# Tr_Final.net
KiCad netlist of a schematic drawn in EAGLE
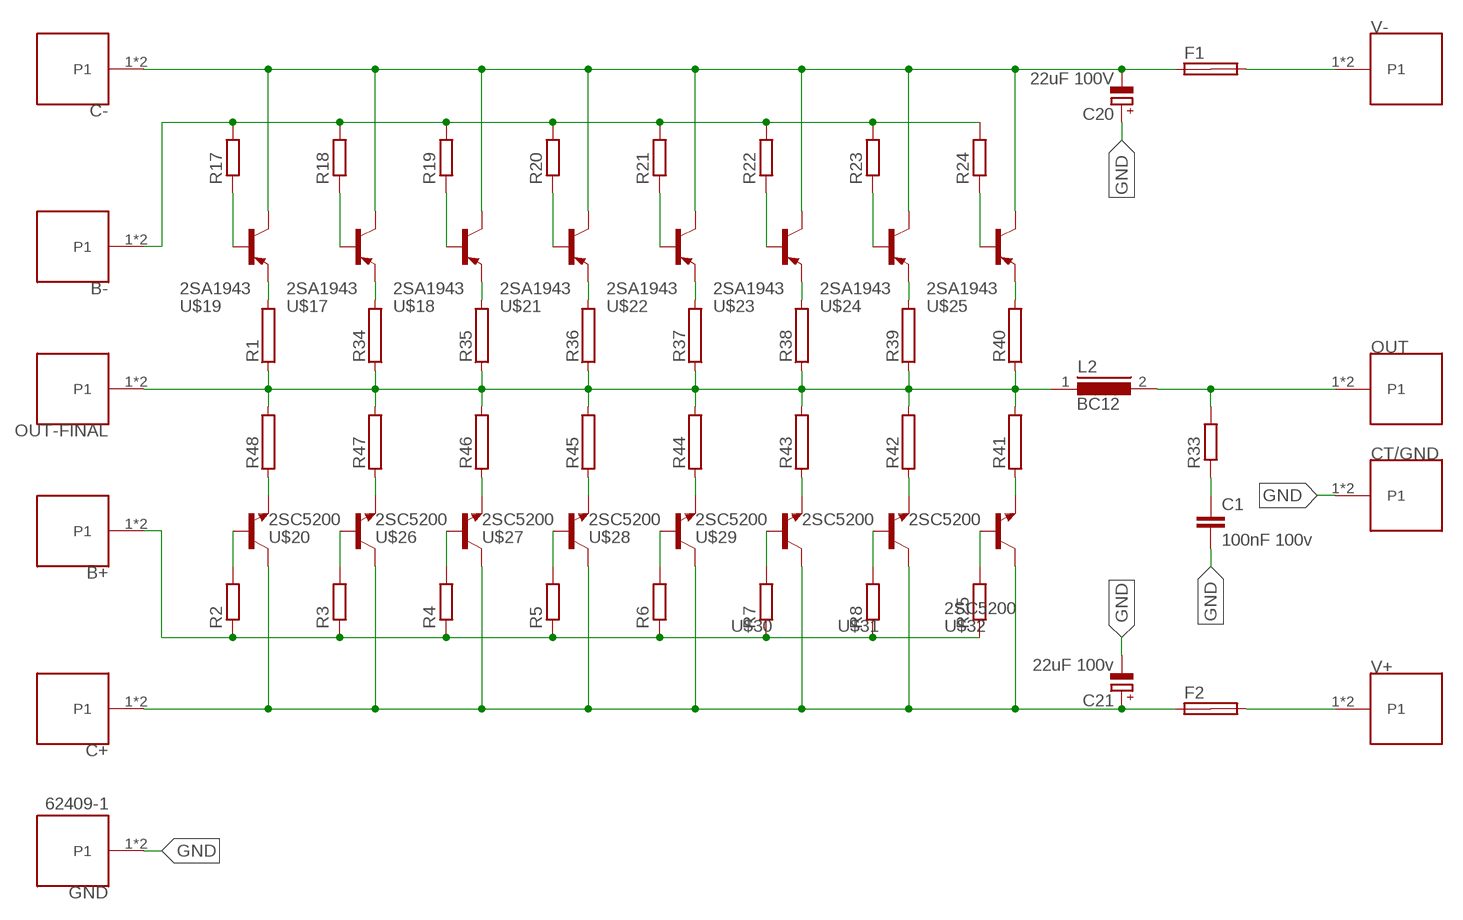
[diagram p0: schematic, sheet 1]

(export (version "E")
  (design (tool "Eeschema 10.0.6"))
  (components
    (comp (ref "B+")
      (value "62409-1")
      (footprint "eagle-import:TE_62409-1")
      (fields (field (name "MF") "TE Connectivity"))
      (libsource (lib "eagle-import") (part "62409-1"))
    )
    (comp (ref "B-")
      (value "62409-1")
      (footprint "eagle-import:TE_62409-1")
      (fields (field (name "MF") "TE Connectivity"))
      (libsource (lib "eagle-import") (part "62409-1"))
    )
    (comp (ref "C+")
      (value "62409-1")
      (footprint "eagle-import:TE_62409-1")
      (fields (field (name "MF") "TE Connectivity"))
      (libsource (lib "eagle-import") (part "62409-1"))
    )
    (comp (ref "C-")
      (value "SKUN")
      (footprint "eagle-import:TE_62409-1")
      (fields (field (name "COMMENT") "62409-1") (field (name "MF") "TE Connectivity"))
      (libsource (lib "eagle-import") (part "62409-1"))
    )
    (comp (ref "C1")
      (value "100nF 100v")
      (footprint "eagle-import:C7.5B5")
      (libsource (lib "eagle-import") (part "C7.5/5"))
    )
    (comp (ref "C20")
      (value "22uF 100V")
      (footprint "eagle-import:E3,5-8")
      (libsource (lib "eagle-import") (part "CPOL-EUE3.5-8"))
    )
    (comp (ref "C21")
      (value "22uF 100v")
      (footprint "eagle-import:E3,5-8")
      (libsource (lib "eagle-import") (part "CPOL-EUE3.5-8"))
    )
    (comp (ref "CT/GND")
      (value "62409-1")
      (footprint "eagle-import:TE_62409-1")
      (fields (field (name "MF") "TE Connectivity"))
      (libsource (lib "eagle-import") (part "62409-1"))
    )
    (comp (ref "F1")
      (value "SHK20L")
      (footprint "eagle-import:SHK20L")
      (libsource (lib "eagle-import") (part "SHK20L"))
    )
    (comp (ref "F2")
      (value "SHK20L")
      (footprint "eagle-import:SHK20L")
      (libsource (lib "eagle-import") (part "SHK20L"))
    )
    (comp (ref "GND")
      (value "62409-1")
      (footprint "eagle-import:TE_62409-1")
      (fields (field (name "MF") "TE Connectivity"))
      (libsource (lib "eagle-import") (part "62409-1"))
    )
    (comp (ref "L2")
      (value "BC12")
      (footprint "eagle-import:BC12")
      (libsource (lib "eagle-import") (part "BC12"))
    )
    (comp (ref "OUT")
      (value "62409-1")
      (footprint "eagle-import:TE_62409-1")
      (fields (field (name "MF") "TE Connectivity"))
      (libsource (lib "eagle-import") (part "62409-1"))
    )
    (comp (ref "OUT-FINAL")
      (value "62409-1")
      (footprint "eagle-import:TE_62409-1")
      (fields (field (name "MF") "TE Connectivity"))
      (libsource (lib "eagle-import") (part "62409-1"))
    )
    (comp (ref "R1")
      (value "RMG100-V")
      (footprint "eagle-import:TO-247-2V")
      (libsource (lib "eagle-import") (part "RMG100-V"))
    )
    (comp (ref "R2")
      (value "R-EU_0207/15")
      (footprint "eagle-import:0207_15")
      (libsource (lib "eagle-import") (part "resistor coba_R-EU_0207/15"))
    )
    (comp (ref "R3")
      (value "R-EU_0207/15")
      (footprint "eagle-import:0207_15")
      (libsource (lib "eagle-import") (part "resistor coba_R-EU_0207/15"))
    )
    (comp (ref "R4")
      (value "R-EU_0207/15")
      (footprint "eagle-import:0207_15")
      (libsource (lib "eagle-import") (part "resistor coba_R-EU_0207/15"))
    )
    (comp (ref "R5")
      (value "R-EU_0207/15")
      (footprint "eagle-import:0207_15")
      (libsource (lib "eagle-import") (part "resistor coba_R-EU_0207/15"))
    )
    (comp (ref "R6")
      (value "R-EU_0207/15")
      (footprint "eagle-import:0207_15")
      (libsource (lib "eagle-import") (part "resistor coba_R-EU_0207/15"))
    )
    (comp (ref "R7")
      (value "R-EU_0207/15")
      (footprint "eagle-import:0207_15")
      (libsource (lib "eagle-import") (part "resistor coba_R-EU_0207/15"))
    )
    (comp (ref "R8")
      (value "R-EU_0207/15")
      (footprint "eagle-import:0207_15")
      (libsource (lib "eagle-import") (part "resistor coba_R-EU_0207/15"))
    )
    (comp (ref "R17")
      (value "R-EU_0207/15")
      (footprint "eagle-import:0207_15")
      (libsource (lib "eagle-import") (part "resistor coba_R-EU_0207/15"))
    )
    (comp (ref "R18")
      (value "R-EU_0207/15")
      (footprint "eagle-import:0207_15")
      (libsource (lib "eagle-import") (part "resistor coba_R-EU_0207/15"))
    )
    (comp (ref "R19")
      (value "R-EU_0207/15")
      (footprint "eagle-import:0207_15")
      (libsource (lib "eagle-import") (part "resistor coba_R-EU_0207/15"))
    )
    (comp (ref "R20")
      (value "R-EU_0207/15")
      (footprint "eagle-import:0207_15")
      (libsource (lib "eagle-import") (part "resistor coba_R-EU_0207/15"))
    )
    (comp (ref "R21")
      (value "R-EU_0207/15")
      (footprint "eagle-import:0207_15")
      (libsource (lib "eagle-import") (part "resistor coba_R-EU_0207/15"))
    )
    (comp (ref "R22")
      (value "R-EU_0207/15")
      (footprint "eagle-import:0207_15")
      (libsource (lib "eagle-import") (part "resistor coba_R-EU_0207/15"))
    )
    (comp (ref "R23")
      (value "R-EU_0207/15")
      (footprint "eagle-import:0207_15")
      (libsource (lib "eagle-import") (part "resistor coba_R-EU_0207/15"))
    )
    (comp (ref "R24")
      (value "R-EU_0207/15")
      (footprint "eagle-import:0207_15")
      (libsource (lib "eagle-import") (part "resistor coba_R-EU_0207/15"))
    )
    (comp (ref "R25")
      (value "R-EU_0207/15")
      (footprint "eagle-import:0207_15")
      (libsource (lib "eagle-import") (part "resistor coba_R-EU_0207/15"))
    )
    (comp (ref "R33")
      (value "R-EU_0617/22")
      (footprint "eagle-import:0617_22")
      (libsource (lib "eagle-import") (part "R-EU_0617/22"))
    )
    (comp (ref "R34")
      (value "RMG100-V")
      (footprint "eagle-import:TO-247-2V")
      (libsource (lib "eagle-import") (part "RMG100-V"))
    )
    (comp (ref "R35")
      (value "RMG100-V")
      (footprint "eagle-import:TO-247-2V")
      (libsource (lib "eagle-import") (part "RMG100-V"))
    )
    (comp (ref "R36")
      (value "RMG100-V")
      (footprint "eagle-import:TO-247-2V")
      (libsource (lib "eagle-import") (part "RMG100-V"))
    )
    (comp (ref "R37")
      (value "RMG100-V")
      (footprint "eagle-import:TO-247-2V")
      (libsource (lib "eagle-import") (part "RMG100-V"))
    )
    (comp (ref "R38")
      (value "RMG100-V")
      (footprint "eagle-import:TO-247-2V")
      (libsource (lib "eagle-import") (part "RMG100-V"))
    )
    (comp (ref "R39")
      (value "RMG100-V")
      (footprint "eagle-import:TO-247-2V")
      (libsource (lib "eagle-import") (part "RMG100-V"))
    )
    (comp (ref "R40")
      (value "RMG100-V")
      (footprint "eagle-import:TO-247-2V")
      (libsource (lib "eagle-import") (part "RMG100-V"))
    )
    (comp (ref "R41")
      (value "RMG100-V")
      (footprint "eagle-import:TO-247-2V")
      (libsource (lib "eagle-import") (part "RMG100-V"))
    )
    (comp (ref "R42")
      (value "RMG100-V")
      (footprint "eagle-import:TO-247-2V")
      (libsource (lib "eagle-import") (part "RMG100-V"))
    )
    (comp (ref "R43")
      (value "RMG100-V")
      (footprint "eagle-import:TO-247-2V")
      (libsource (lib "eagle-import") (part "RMG100-V"))
    )
    (comp (ref "R44")
      (value "RMG100-V")
      (footprint "eagle-import:TO-247-2V")
      (libsource (lib "eagle-import") (part "RMG100-V"))
    )
    (comp (ref "R45")
      (value "RMG100-V")
      (footprint "eagle-import:TO-247-2V")
      (libsource (lib "eagle-import") (part "RMG100-V"))
    )
    (comp (ref "R46")
      (value "RMG100-V")
      (footprint "eagle-import:TO-247-2V")
      (libsource (lib "eagle-import") (part "RMG100-V"))
    )
    (comp (ref "R47")
      (value "RMG100-V")
      (footprint "eagle-import:TO-247-2V")
      (libsource (lib "eagle-import") (part "RMG100-V"))
    )
    (comp (ref "R48")
      (value "RMG100-V")
      (footprint "eagle-import:TO-247-2V")
      (libsource (lib "eagle-import") (part "RMG100-V"))
    )
    (comp (ref "U$17")
      (value "2SA1943")
      (footprint "eagle-import:TO-264")
      (libsource (lib "eagle-import") (part "2SA1943"))
    )
    (comp (ref "U$18")
      (value "2SA1943")
      (footprint "eagle-import:TO-264")
      (libsource (lib "eagle-import") (part "2SA1943"))
    )
    (comp (ref "U$19")
      (value "2SA1943")
      (footprint "eagle-import:TO-264")
      (libsource (lib "eagle-import") (part "2SA1943"))
    )
    (comp (ref "U$20")
      (value "2SC5200")
      (footprint "eagle-import:TO-264")
      (libsource (lib "eagle-import") (part "2SC5200"))
    )
    (comp (ref "U$21")
      (value "2SA1943")
      (footprint "eagle-import:TO-264")
      (libsource (lib "eagle-import") (part "2SA1943"))
    )
    (comp (ref "U$22")
      (value "2SA1943")
      (footprint "eagle-import:TO-264")
      (libsource (lib "eagle-import") (part "2SA1943"))
    )
    (comp (ref "U$23")
      (value "2SA1943")
      (footprint "eagle-import:TO-264")
      (libsource (lib "eagle-import") (part "2SA1943"))
    )
    (comp (ref "U$24")
      (value "2SA1943")
      (footprint "eagle-import:TO-264")
      (libsource (lib "eagle-import") (part "2SA1943"))
    )
    (comp (ref "U$25")
      (value "2SA1943")
      (footprint "eagle-import:TO-264")
      (libsource (lib "eagle-import") (part "2SA1943"))
    )
    (comp (ref "U$26")
      (value "2SC5200")
      (footprint "eagle-import:TO-264")
      (libsource (lib "eagle-import") (part "2SC5200"))
    )
    (comp (ref "U$27")
      (value "2SC5200")
      (footprint "eagle-import:TO-264")
      (libsource (lib "eagle-import") (part "2SC5200"))
    )
    (comp (ref "U$28")
      (value "2SC5200")
      (footprint "eagle-import:TO-264")
      (libsource (lib "eagle-import") (part "2SC5200"))
    )
    (comp (ref "U$29")
      (value "2SC5200")
      (footprint "eagle-import:TO-264")
      (libsource (lib "eagle-import") (part "2SC5200"))
    )
    (comp (ref "U$30")
      (value "2SC5200")
      (footprint "eagle-import:TO-264")
      (libsource (lib "eagle-import") (part "2SC5200"))
    )
    (comp (ref "U$31")
      (value "2SC5200")
      (footprint "eagle-import:TO-264")
      (libsource (lib "eagle-import") (part "2SC5200"))
    )
    (comp (ref "U$32")
      (value "2SC5200")
      (footprint "eagle-import:TO-264")
      (libsource (lib "eagle-import") (part "2SC5200"))
    )
    (comp (ref "V+")
      (value "62409-1")
      (footprint "eagle-import:TE_62409-1")
      (fields (field (name "MF") "TE Connectivity"))
      (libsource (lib "eagle-import") (part "62409-1"))
    )
    (comp (ref "V-")
      (value "62409-1")
      (footprint "eagle-import:TE_62409-1")
      (fields (field (name "MF") "TE Connectivity"))
      (libsource (lib "eagle-import") (part "62409-1"))
    )
  )
  (nets
    (net (code "1") (name "GND") (class "Default")
      (node (ref "C1") (pin "2") (pinfunction "2_2") (pintype "passive"))
      (node (ref "C20") (pin "+") (pinfunction "+_+") (pintype "passive"))
      (node (ref "C21") (pin "-") (pinfunction "-_-") (pintype "passive"))
      (node (ref "CT/GND") (pin "1") (pinfunction "P1_1") (pintype "passive"))
      (node (ref "CT/GND") (pin "2") (pinfunction "P1_2") (pintype "passive"))
      (node (ref "GND") (pin "1") (pinfunction "P1_1") (pintype "passive"))
      (node (ref "GND") (pin "2") (pinfunction "P1_2") (pintype "passive"))
    )
    (net (code "2") (name "Net-(B+-P1-Pad1)") (class "Default")
      (node (ref "B+") (pin "1") (pinfunction "P1_1") (pintype "passive"))
      (node (ref "B+") (pin "2") (pinfunction "P1_2") (pintype "passive"))
      (node (ref "R2") (pin "1") (pinfunction "1_1") (pintype "passive"))
      (node (ref "R25") (pin "1") (pinfunction "1_1") (pintype "passive"))
      (node (ref "R3") (pin "1") (pinfunction "1_1") (pintype "passive"))
      (node (ref "R4") (pin "1") (pinfunction "1_1") (pintype "passive"))
      (node (ref "R5") (pin "1") (pinfunction "1_1") (pintype "passive"))
      (node (ref "R6") (pin "1") (pinfunction "1_1") (pintype "passive"))
      (node (ref "R7") (pin "1") (pinfunction "1_1") (pintype "passive"))
      (node (ref "R8") (pin "1") (pinfunction "1_1") (pintype "passive"))
    )
    (net (code "3") (name "Net-(B--P1-Pad1)") (class "Default")
      (node (ref "B-") (pin "1") (pinfunction "P1_1") (pintype "passive"))
      (node (ref "B-") (pin "2") (pinfunction "P1_2") (pintype "passive"))
      (node (ref "R17") (pin "2") (pinfunction "2_2") (pintype "passive"))
      (node (ref "R18") (pin "2") (pinfunction "2_2") (pintype "passive"))
      (node (ref "R19") (pin "2") (pinfunction "2_2") (pintype "passive"))
      (node (ref "R20") (pin "2") (pinfunction "2_2") (pintype "passive"))
      (node (ref "R21") (pin "2") (pinfunction "2_2") (pintype "passive"))
      (node (ref "R22") (pin "2") (pinfunction "2_2") (pintype "passive"))
      (node (ref "R23") (pin "2") (pinfunction "2_2") (pintype "passive"))
      (node (ref "R24") (pin "2") (pinfunction "2_2") (pintype "passive"))
    )
    (net (code "4") (name "Net-(C+-P1-Pad1)") (class "Default")
      (node (ref "C+") (pin "1") (pinfunction "P1_1") (pintype "passive"))
      (node (ref "C+") (pin "2") (pinfunction "P1_2") (pintype "passive"))
      (node (ref "C21") (pin "+") (pinfunction "+_+") (pintype "passive"))
      (node (ref "F2") (pin "1A") (pinfunction "1A_1A") (pintype "passive"))
      (node (ref "U$20") (pin "C") (pinfunction "C_C") (pintype "passive"))
      (node (ref "U$26") (pin "C") (pinfunction "C_C") (pintype "passive"))
      (node (ref "U$27") (pin "C") (pinfunction "C_C") (pintype "passive"))
      (node (ref "U$28") (pin "C") (pinfunction "C_C") (pintype "passive"))
      (node (ref "U$29") (pin "C") (pinfunction "C_C") (pintype "passive"))
      (node (ref "U$30") (pin "C") (pinfunction "C_C") (pintype "passive"))
      (node (ref "U$31") (pin "C") (pinfunction "C_C") (pintype "passive"))
      (node (ref "U$32") (pin "C") (pinfunction "C_C") (pintype "passive"))
    )
    (net (code "5") (name "Net-(C--P1-Pad1)") (class "Default")
      (node (ref "C-") (pin "1") (pinfunction "P1_1") (pintype "passive"))
      (node (ref "C-") (pin "2") (pinfunction "P1_2") (pintype "passive"))
      (node (ref "C20") (pin "-") (pinfunction "-_-") (pintype "passive"))
      (node (ref "F1") (pin "1A") (pinfunction "1A_1A") (pintype "passive"))
      (node (ref "U$17") (pin "C") (pinfunction "C_C") (pintype "passive"))
      (node (ref "U$18") (pin "C") (pinfunction "C_C") (pintype "passive"))
      (node (ref "U$19") (pin "C") (pinfunction "C_C") (pintype "passive"))
      (node (ref "U$21") (pin "C") (pinfunction "C_C") (pintype "passive"))
      (node (ref "U$22") (pin "C") (pinfunction "C_C") (pintype "passive"))
      (node (ref "U$23") (pin "C") (pinfunction "C_C") (pintype "passive"))
      (node (ref "U$24") (pin "C") (pinfunction "C_C") (pintype "passive"))
      (node (ref "U$25") (pin "C") (pinfunction "C_C") (pintype "passive"))
    )
    (net (code "6") (name "Net-(C1-Pad1)") (class "Default")
      (node (ref "C1") (pin "1") (pinfunction "1_1") (pintype "passive"))
      (node (ref "R33") (pin "1") (pinfunction "1_1") (pintype "passive"))
    )
    (net (code "7") (name "Net-(F1-Pad2A)") (class "Default")
      (node (ref "F1") (pin "2A") (pinfunction "2A_2A") (pintype "passive"))
      (node (ref "V-") (pin "1") (pinfunction "P1_1") (pintype "passive"))
      (node (ref "V-") (pin "2") (pinfunction "P1_2") (pintype "passive"))
    )
    (net (code "8") (name "Net-(F2-Pad2A)") (class "Default")
      (node (ref "F2") (pin "2A") (pinfunction "2A_2A") (pintype "passive"))
      (node (ref "V+") (pin "1") (pinfunction "P1_1") (pintype "passive"))
      (node (ref "V+") (pin "2") (pinfunction "P1_2") (pintype "passive"))
    )
    (net (code "9") (name "Net-(L2-Pad1)") (class "Default")
      (node (ref "L2") (pin "1") (pinfunction "1_1") (pintype "passive"))
      (node (ref "OUT-FINAL") (pin "1") (pinfunction "P1_1") (pintype "passive"))
      (node (ref "OUT-FINAL") (pin "2") (pinfunction "P1_2") (pintype "passive"))
      (node (ref "R1") (pin "1") (pinfunction "1_1") (pintype "passive"))
      (node (ref "R34") (pin "1") (pinfunction "1_1") (pintype "passive"))
      (node (ref "R35") (pin "1") (pinfunction "1_1") (pintype "passive"))
      (node (ref "R36") (pin "1") (pinfunction "1_1") (pintype "passive"))
      (node (ref "R37") (pin "1") (pinfunction "1_1") (pintype "passive"))
      (node (ref "R38") (pin "1") (pinfunction "1_1") (pintype "passive"))
      (node (ref "R39") (pin "1") (pinfunction "1_1") (pintype "passive"))
      (node (ref "R40") (pin "1") (pinfunction "1_1") (pintype "passive"))
      (node (ref "R41") (pin "2") (pinfunction "2_2") (pintype "passive"))
      (node (ref "R42") (pin "2") (pinfunction "2_2") (pintype "passive"))
      (node (ref "R43") (pin "2") (pinfunction "2_2") (pintype "passive"))
      (node (ref "R44") (pin "2") (pinfunction "2_2") (pintype "passive"))
      (node (ref "R45") (pin "2") (pinfunction "2_2") (pintype "passive"))
      (node (ref "R46") (pin "2") (pinfunction "2_2") (pintype "passive"))
      (node (ref "R47") (pin "2") (pinfunction "2_2") (pintype "passive"))
      (node (ref "R48") (pin "2") (pinfunction "2_2") (pintype "passive"))
    )
    (net (code "10") (name "Net-(L2-Pad2)") (class "Default")
      (node (ref "L2") (pin "2") (pinfunction "2_2") (pintype "passive"))
      (node (ref "OUT") (pin "1") (pinfunction "P1_1") (pintype "passive"))
      (node (ref "OUT") (pin "2") (pinfunction "P1_2") (pintype "passive"))
      (node (ref "R33") (pin "2") (pinfunction "2_2") (pintype "passive"))
    )
    (net (code "11") (name "Net-(R1-Pad2)") (class "Default")
      (node (ref "R1") (pin "2") (pinfunction "2_2") (pintype "passive"))
      (node (ref "U$19") (pin "E") (pinfunction "E_E") (pintype "passive"))
    )
    (net (code "12") (name "Net-(R2-Pad2)") (class "Default")
      (node (ref "R2") (pin "2") (pinfunction "2_2") (pintype "passive"))
      (node (ref "U$20") (pin "B") (pinfunction "B_B") (pintype "passive"))
    )
    (net (code "13") (name "Net-(R3-Pad2)") (class "Default")
      (node (ref "R3") (pin "2") (pinfunction "2_2") (pintype "passive"))
      (node (ref "U$26") (pin "B") (pinfunction "B_B") (pintype "passive"))
    )
    (net (code "14") (name "Net-(R4-Pad2)") (class "Default")
      (node (ref "R4") (pin "2") (pinfunction "2_2") (pintype "passive"))
      (node (ref "U$27") (pin "B") (pinfunction "B_B") (pintype "passive"))
    )
    (net (code "15") (name "Net-(R5-Pad2)") (class "Default")
      (node (ref "R5") (pin "2") (pinfunction "2_2") (pintype "passive"))
      (node (ref "U$28") (pin "B") (pinfunction "B_B") (pintype "passive"))
    )
    (net (code "16") (name "Net-(R6-Pad2)") (class "Default")
      (node (ref "R6") (pin "2") (pinfunction "2_2") (pintype "passive"))
      (node (ref "U$29") (pin "B") (pinfunction "B_B") (pintype "passive"))
    )
    (net (code "17") (name "Net-(R7-Pad2)") (class "Default")
      (node (ref "R7") (pin "2") (pinfunction "2_2") (pintype "passive"))
      (node (ref "U$30") (pin "B") (pinfunction "B_B") (pintype "passive"))
    )
    (net (code "18") (name "Net-(R8-Pad2)") (class "Default")
      (node (ref "R8") (pin "2") (pinfunction "2_2") (pintype "passive"))
      (node (ref "U$31") (pin "B") (pinfunction "B_B") (pintype "passive"))
    )
    (net (code "19") (name "Net-(R17-Pad1)") (class "Default")
      (node (ref "R17") (pin "1") (pinfunction "1_1") (pintype "passive"))
      (node (ref "U$19") (pin "B") (pinfunction "B_B") (pintype "passive"))
    )
    (net (code "20") (name "Net-(R18-Pad1)") (class "Default")
      (node (ref "R18") (pin "1") (pinfunction "1_1") (pintype "passive"))
      (node (ref "U$17") (pin "B") (pinfunction "B_B") (pintype "passive"))
    )
    (net (code "21") (name "Net-(R19-Pad1)") (class "Default")
      (node (ref "R19") (pin "1") (pinfunction "1_1") (pintype "passive"))
      (node (ref "U$18") (pin "B") (pinfunction "B_B") (pintype "passive"))
    )
    (net (code "22") (name "Net-(R20-Pad1)") (class "Default")
      (node (ref "R20") (pin "1") (pinfunction "1_1") (pintype "passive"))
      (node (ref "U$21") (pin "B") (pinfunction "B_B") (pintype "passive"))
    )
    (net (code "23") (name "Net-(R21-Pad1)") (class "Default")
      (node (ref "R21") (pin "1") (pinfunction "1_1") (pintype "passive"))
      (node (ref "U$22") (pin "B") (pinfunction "B_B") (pintype "passive"))
    )
    (net (code "24") (name "Net-(R22-Pad1)") (class "Default")
      (node (ref "R22") (pin "1") (pinfunction "1_1") (pintype "passive"))
      (node (ref "U$23") (pin "B") (pinfunction "B_B") (pintype "passive"))
    )
    (net (code "25") (name "Net-(R23-Pad1)") (class "Default")
      (node (ref "R23") (pin "1") (pinfunction "1_1") (pintype "passive"))
      (node (ref "U$24") (pin "B") (pinfunction "B_B") (pintype "passive"))
    )
    (net (code "26") (name "Net-(R24-Pad1)") (class "Default")
      (node (ref "R24") (pin "1") (pinfunction "1_1") (pintype "passive"))
      (node (ref "U$25") (pin "B") (pinfunction "B_B") (pintype "passive"))
    )
    (net (code "27") (name "Net-(R25-Pad2)") (class "Default")
      (node (ref "R25") (pin "2") (pinfunction "2_2") (pintype "passive"))
      (node (ref "U$32") (pin "B") (pinfunction "B_B") (pintype "passive"))
    )
    (net (code "28") (name "Net-(R34-Pad2)") (class "Default")
      (node (ref "R34") (pin "2") (pinfunction "2_2") (pintype "passive"))
      (node (ref "U$17") (pin "E") (pinfunction "E_E") (pintype "passive"))
    )
    (net (code "29") (name "Net-(R35-Pad2)") (class "Default")
      (node (ref "R35") (pin "2") (pinfunction "2_2") (pintype "passive"))
      (node (ref "U$18") (pin "E") (pinfunction "E_E") (pintype "passive"))
    )
    (net (code "30") (name "Net-(R36-Pad2)") (class "Default")
      (node (ref "R36") (pin "2") (pinfunction "2_2") (pintype "passive"))
      (node (ref "U$21") (pin "E") (pinfunction "E_E") (pintype "passive"))
    )
    (net (code "31") (name "Net-(R37-Pad2)") (class "Default")
      (node (ref "R37") (pin "2") (pinfunction "2_2") (pintype "passive"))
      (node (ref "U$22") (pin "E") (pinfunction "E_E") (pintype "passive"))
    )
    (net (code "32") (name "Net-(R38-Pad2)") (class "Default")
      (node (ref "R38") (pin "2") (pinfunction "2_2") (pintype "passive"))
      (node (ref "U$23") (pin "E") (pinfunction "E_E") (pintype "passive"))
    )
    (net (code "33") (name "Net-(R39-Pad2)") (class "Default")
      (node (ref "R39") (pin "2") (pinfunction "2_2") (pintype "passive"))
      (node (ref "U$24") (pin "E") (pinfunction "E_E") (pintype "passive"))
    )
    (net (code "34") (name "Net-(R40-Pad2)") (class "Default")
      (node (ref "R40") (pin "2") (pinfunction "2_2") (pintype "passive"))
      (node (ref "U$25") (pin "E") (pinfunction "E_E") (pintype "passive"))
    )
    (net (code "35") (name "Net-(R41-Pad1)") (class "Default")
      (node (ref "R41") (pin "1") (pinfunction "1_1") (pintype "passive"))
      (node (ref "U$32") (pin "E") (pinfunction "E_E") (pintype "passive"))
    )
    (net (code "36") (name "Net-(R42-Pad1)") (class "Default")
      (node (ref "R42") (pin "1") (pinfunction "1_1") (pintype "passive"))
      (node (ref "U$31") (pin "E") (pinfunction "E_E") (pintype "passive"))
    )
    (net (code "37") (name "Net-(R43-Pad1)") (class "Default")
      (node (ref "R43") (pin "1") (pinfunction "1_1") (pintype "passive"))
      (node (ref "U$30") (pin "E") (pinfunction "E_E") (pintype "passive"))
    )
    (net (code "38") (name "Net-(R44-Pad1)") (class "Default")
      (node (ref "R44") (pin "1") (pinfunction "1_1") (pintype "passive"))
      (node (ref "U$29") (pin "E") (pinfunction "E_E") (pintype "passive"))
    )
    (net (code "39") (name "Net-(R45-Pad1)") (class "Default")
      (node (ref "R45") (pin "1") (pinfunction "1_1") (pintype "passive"))
      (node (ref "U$28") (pin "E") (pinfunction "E_E") (pintype "passive"))
    )
    (net (code "40") (name "Net-(R46-Pad1)") (class "Default")
      (node (ref "R46") (pin "1") (pinfunction "1_1") (pintype "passive"))
      (node (ref "U$27") (pin "E") (pinfunction "E_E") (pintype "passive"))
    )
    (net (code "41") (name "Net-(R47-Pad1)") (class "Default")
      (node (ref "R47") (pin "1") (pinfunction "1_1") (pintype "passive"))
      (node (ref "U$26") (pin "E") (pinfunction "E_E") (pintype "passive"))
    )
    (net (code "42") (name "Net-(R48-Pad1)") (class "Default")
      (node (ref "R48") (pin "1") (pinfunction "1_1") (pintype "passive"))
      (node (ref "U$20") (pin "E") (pinfunction "E_E") (pintype "passive"))
    )
    (net (code "43") (name "unconnected-(F1-Pad1B)") (class "Default")
      (node (ref "F1") (pin "1B") (pinfunction "1B_1B") (pintype "passive"))
    )
    (net (code "44") (name "unconnected-(F1-Pad2B)") (class "Default")
      (node (ref "F1") (pin "2B") (pinfunction "2B_2B") (pintype "passive"))
    )
    (net (code "45") (name "unconnected-(F2-Pad1B)") (class "Default")
      (node (ref "F2") (pin "1B") (pinfunction "1B_1B") (pintype "passive"))
    )
    (net (code "46") (name "unconnected-(F2-Pad2B)") (class "Default")
      (node (ref "F2") (pin "2B") (pinfunction "2B_2B") (pintype "passive"))
    )
  )
)
